# fact-atmega32u4.net
KiCad netlist of a schematic drawn in EAGLE
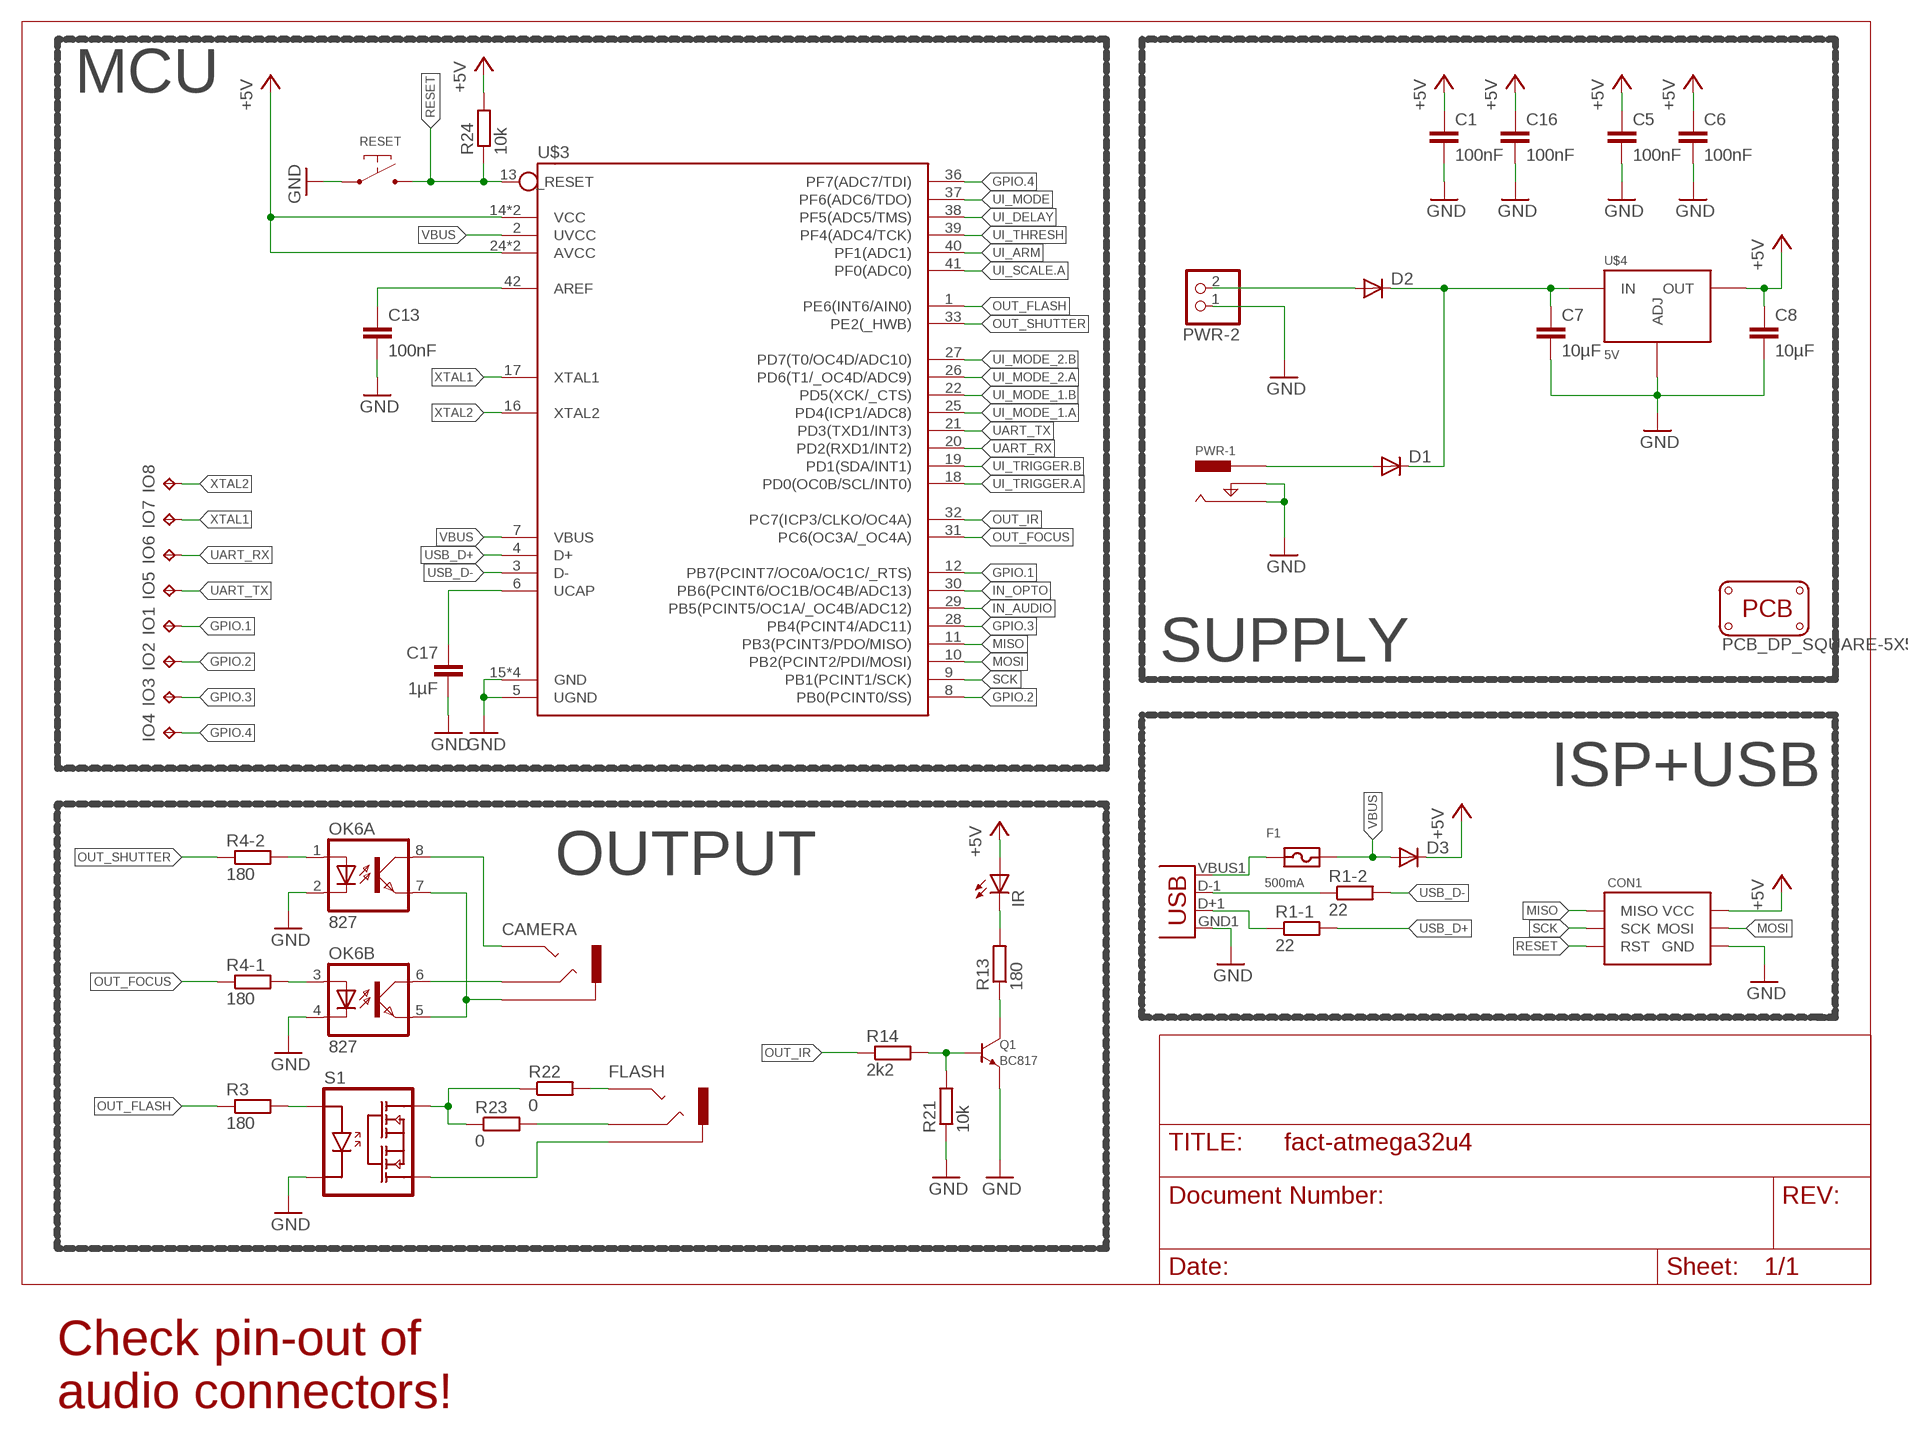
[diagram p0: schematic, sheet 1, part 1 of 2]
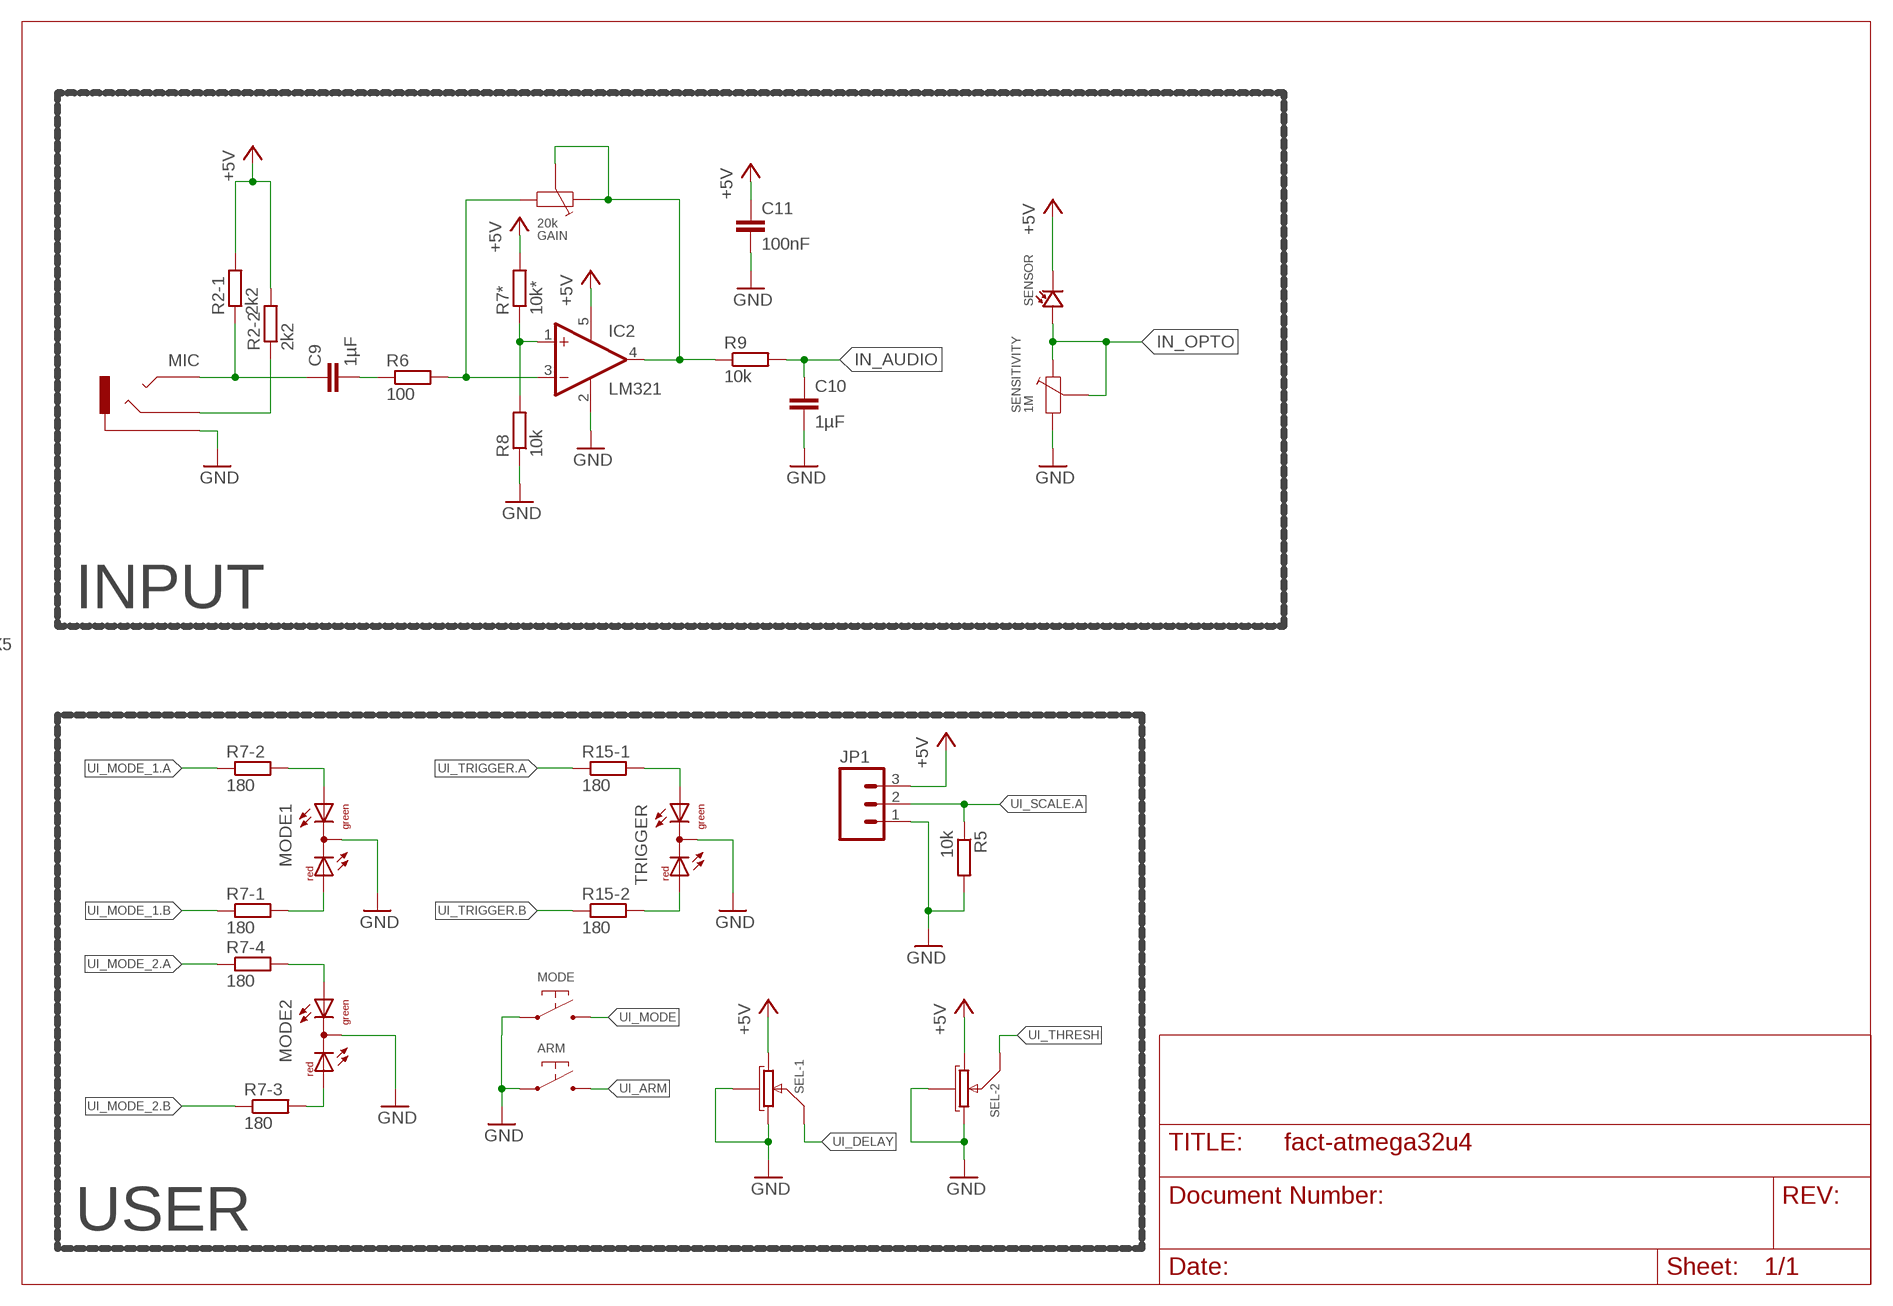
[diagram p1: schematic, sheet 1, part 2 of 2]

(export (version "E")
  (design (tool "Eeschema 10.0.6"))
  (components
    (comp (ref "ARM")
      (value "SWITCH-DEFAULT_OFF-DEFAULT")
      (footprint "eagle-import:SWITCH-GENERIC-4_PIN")
      (libsource (lib "eagle-import") (part "SWITCH-DEFAULT_OFF-DEFAULT"))
    )
    (comp (ref "C1")
      (value "100nF")
      (footprint "eagle-import:C0603")
      (libsource (lib "eagle-import") (part "C-EUC0603"))
    )
    (comp (ref "C5")
      (value "100nF")
      (footprint "eagle-import:C0603")
      (libsource (lib "eagle-import") (part "C-EUC0603"))
    )
    (comp (ref "C6")
      (value "100nF")
      (footprint "eagle-import:C0603")
      (libsource (lib "eagle-import") (part "C-EUC0603"))
    )
    (comp (ref "C7")
      (value "10µF")
      (footprint "eagle-import:C0603")
      (libsource (lib "eagle-import") (part "C-EUC0603"))
    )
    (comp (ref "C8")
      (value "10µF")
      (footprint "eagle-import:C0603")
      (libsource (lib "eagle-import") (part "C-EUC0603"))
    )
    (comp (ref "C9")
      (value "1µF")
      (footprint "eagle-import:C0603")
      (libsource (lib "eagle-import") (part "C-EUC0603"))
    )
    (comp (ref "C10")
      (value "1µF")
      (footprint "eagle-import:C0603")
      (libsource (lib "eagle-import") (part "C-EUC0603"))
    )
    (comp (ref "C11")
      (value "100nF")
      (footprint "eagle-import:C0603")
      (libsource (lib "eagle-import") (part "C-EUC0603"))
    )
    (comp (ref "C13")
      (value "100nF")
      (footprint "eagle-import:C0603")
      (libsource (lib "eagle-import") (part "C-EUC0603"))
    )
    (comp (ref "C16")
      (value "100nF")
      (footprint "eagle-import:C0603")
      (libsource (lib "eagle-import") (part "C-EUC0603"))
    )
    (comp (ref "C17")
      (value "1µF")
      (footprint "eagle-import:C0603")
      (libsource (lib "eagle-import") (part "C-EUC0603"))
    )
    (comp (ref "CAMERA")
      (value "AUDIO-STEREO2MM5")
      (footprint "eagle-import:AUDIO-STEREO-2MM5-SJ1-2503A")
      (libsource (lib "eagle-import") (part "AUDIO-STEREO2MM5"))
    )
    (comp (ref "CON1")
      (value "ISP-6_PIN-POGO")
      (footprint "eagle-import:POGO-1.27-6_PIN-MADWORM")
      (libsource (lib "eagle-import") (part "ISP-6_PIN-POGO"))
    )
    (comp (ref "D1")
      (value "DIODESOD")
      (footprint "eagle-import:SOD-323")
      (libsource (lib "eagle-import") (part "DIODESOD"))
    )
    (comp (ref "D2")
      (value "DIODESOD")
      (footprint "eagle-import:SOD-323")
      (libsource (lib "eagle-import") (part "DIODESOD"))
    )
    (comp (ref "D3")
      (value "DIODESOD")
      (footprint "eagle-import:SOD-323")
      (libsource (lib "eagle-import") (part "DIODESOD"))
    )
    (comp (ref "F1")
      (value "500mA")
      (footprint "eagle-import:SMD-0805")
      (libsource (lib "eagle-import") (part "FUSE0805"))
    )
    (comp (ref "FLASH")
      (value "AUDIO-STEREODEALEXTREME")
      (footprint "eagle-import:AUDIO-STEREO-3MM5-ST-009")
      (libsource (lib "eagle-import") (part "AUDIO-STEREODEALEXTREME"))
    )
    (comp (ref "GAIN")
      (value "20k")
      (footprint "eagle-import:TRIM-POT-CA6-VS5")
      (libsource (lib "eagle-import") (part "TRIM-POT"))
    )
    (comp (ref "IC2")
      (value "LM321")
      (footprint "eagle-import:SOT23-5")
      (libsource (lib "eagle-import") (part "LM321?MF"))
    )
    (comp (ref "IO1")
      (value "TPTP15R")
      (footprint "eagle-import:TP15R")
      (libsource (lib "eagle-import") (part "TPTP15R"))
    )
    (comp (ref "IO2")
      (value "TPTP15R")
      (footprint "eagle-import:TP15R")
      (libsource (lib "eagle-import") (part "TPTP15R"))
    )
    (comp (ref "IO3")
      (value "TPTP15R")
      (footprint "eagle-import:TP15R")
      (libsource (lib "eagle-import") (part "TPTP15R"))
    )
    (comp (ref "IO4")
      (value "TPTP15R")
      (footprint "eagle-import:TP15R")
      (libsource (lib "eagle-import") (part "TPTP15R"))
    )
    (comp (ref "IO5")
      (value "TPTP15R")
      (footprint "eagle-import:TP15R")
      (libsource (lib "eagle-import") (part "TPTP15R"))
    )
    (comp (ref "IO6")
      (value "TPTP15R")
      (footprint "eagle-import:TP15R")
      (libsource (lib "eagle-import") (part "TPTP15R"))
    )
    (comp (ref "IO7")
      (value "TPTP15R")
      (footprint "eagle-import:TP15R")
      (libsource (lib "eagle-import") (part "TPTP15R"))
    )
    (comp (ref "IO8")
      (value "TPTP15R")
      (footprint "eagle-import:TP15R")
      (libsource (lib "eagle-import") (part "TPTP15R"))
    )
    (comp (ref "IR")
      (value "LED5MM")
      (footprint "eagle-import:LED5MM")
      (libsource (lib "eagle-import") (part "LED5MM"))
    )
    (comp (ref "JP1")
      (value "M03LOCK")
      (footprint "eagle-import:1X03_LOCK")
      (libsource (lib "eagle-import") (part "M03LOCK"))
    )
    (comp (ref "MIC")
      (value "AUDIO-STEREODEALEXTREME")
      (footprint "eagle-import:AUDIO-STEREO-3MM5-ST-009")
      (libsource (lib "eagle-import") (part "AUDIO-STEREODEALEXTREME"))
    )
    (comp (ref "MODE")
      (value "SWITCH-DEFAULT_OFF-DEFAULT")
      (footprint "eagle-import:SWITCH-GENERIC-4_PIN")
      (libsource (lib "eagle-import") (part "SWITCH-DEFAULT_OFF-DEFAULT"))
    )
    (comp (ref "MODE1")
      (value "DUOLED-RG-C")
      (footprint "eagle-import:DUOLED-C-5MM")
      (libsource (lib "eagle-import") (part "DUOLED-RG-C"))
    )
    (comp (ref "MODE2")
      (value "DUOLED-RG-C")
      (footprint "eagle-import:DUOLED-C-5MM")
      (libsource (lib "eagle-import") (part "DUOLED-RG-C"))
    )
    (comp (ref "OK6")
      (value "827")
      (footprint "eagle-import:SMD08")
      (libsource (lib "eagle-import") (part "OPTOCOUPLER-PC827SMD"))
    )
    (comp (ref "PCB1")
      (value "PCB_DP_SQUARE-5X5")
      (footprint "eagle-import:DP5050_V1")
      (libsource (lib "eagle-import") (part "PCB_DP_SQUARE-5X5"))
    )
    (comp (ref "PWR-1")
      (value "POWER-BARREL_JACKEBAY")
      (footprint "eagle-import:POWER-BARREL-2MM1-EBAY")
      (libsource (lib "eagle-import") (part "POWER-BARREL_JACKEBAY"))
    )
    (comp (ref "PWR-2")
      (value "PINHD-1X2")
      (footprint "eagle-import:1X02")
      (libsource (lib "eagle-import") (part "PINHD-1X2"))
    )
    (comp (ref "Q1")
      (value "BC817")
      (footprint "eagle-import:SOT23")
      (libsource (lib "eagle-import") (part "TRANSISTOR-NPN-GENERIC-BEC"))
    )
    (comp (ref "R1")
      (value "22")
      (footprint "eagle-import:R-ARRAY-2X-0603")
      (libsource (lib "eagle-import") (part "R-ARRAY-2X-0603"))
    )
    (comp (ref "R2")
      (value "2k2")
      (footprint "eagle-import:R-ARRAY-2X-0603")
      (libsource (lib "eagle-import") (part "R-ARRAY-2X-0603"))
    )
    (comp (ref "R3")
      (value "180")
      (footprint "eagle-import:R0603")
      (libsource (lib "eagle-import") (part "R-EU_R0603"))
    )
    (comp (ref "R4")
      (value "180")
      (footprint "eagle-import:R-ARRAY-2X-0603")
      (libsource (lib "eagle-import") (part "R-ARRAY-2X-0603"))
    )
    (comp (ref "R5")
      (value "10k")
      (footprint "eagle-import:R0603")
      (libsource (lib "eagle-import") (part "R-EU_R0603"))
    )
    (comp (ref "R6")
      (value "100")
      (footprint "eagle-import:R0603")
      (libsource (lib "eagle-import") (part "R-EU_R0603"))
    )
    (comp (ref "R7")
      (value "180")
      (footprint "eagle-import:R-ARRAY-4X-CTS-0603")
      (libsource (lib "eagle-import") (part "R-ARRAY-4X0603"))
    )
    (comp (ref "R7*")
      (value "10k*")
      (footprint "eagle-import:R0603")
      (libsource (lib "eagle-import") (part "R-EU_R0603"))
    )
    (comp (ref "R8")
      (value "10k")
      (footprint "eagle-import:R0603")
      (libsource (lib "eagle-import") (part "R-EU_R0603"))
    )
    (comp (ref "R9")
      (value "10k")
      (footprint "eagle-import:R0603")
      (libsource (lib "eagle-import") (part "R-EU_R0603"))
    )
    (comp (ref "R13")
      (value "180")
      (footprint "eagle-import:R0603")
      (libsource (lib "eagle-import") (part "R-EU_R0603"))
    )
    (comp (ref "R14")
      (value "2k2")
      (footprint "eagle-import:R0603")
      (libsource (lib "eagle-import") (part "R-EU_R0603"))
    )
    (comp (ref "R15")
      (value "180")
      (footprint "eagle-import:R-ARRAY-2X-0603")
      (libsource (lib "eagle-import") (part "R-ARRAY-2X-0603"))
    )
    (comp (ref "R21")
      (value "10k")
      (footprint "eagle-import:R0603")
      (libsource (lib "eagle-import") (part "R-EU_R0603"))
    )
    (comp (ref "R22")
      (value "0")
      (footprint "eagle-import:R1206")
      (libsource (lib "eagle-import") (part "rcl_R-EU_R1206"))
    )
    (comp (ref "R23")
      (value "0")
      (footprint "eagle-import:R1206")
      (libsource (lib "eagle-import") (part "rcl_R-EU_R1206"))
    )
    (comp (ref "R24")
      (value "10k")
      (footprint "eagle-import:R0603")
      (libsource (lib "eagle-import") (part "R-EU_R0603"))
    )
    (comp (ref "RESET")
      (value "SWITCH-DEFAULT_OFF-SMD-2_PIN")
      (footprint "eagle-import:SWITCH-SMD-2_PIN-DX")
      (libsource (lib "eagle-import") (part "SWITCH-DEFAULT_OFF-SMD-2_PIN"))
    )
    (comp (ref "S1")
      (value "RELAYLH1500")
      (footprint "eagle-import:SMD-06")
      (libsource (lib "eagle-import") (part "RELAYLH1500"))
    )
    (comp (ref "SEL")
      (value "DUAL-POT")
      (footprint "eagle-import:POT-DUAL-P090")
      (libsource (lib "eagle-import") (part "DUAL-POT"))
    )
    (comp (ref "SENSITIVITY")
      (value "1M")
      (footprint "eagle-import:TRIM-POT-CA6-VS5")
      (libsource (lib "eagle-import") (part "TRIM-POT"))
    )
    (comp (ref "SENSOR")
      (value "PHOTODIODE")
      (footprint "eagle-import:LED-5MM")
      (libsource (lib "eagle-import") (part "PHOTODIODE"))
    )
    (comp (ref "TRIGGER")
      (value "DUOLED-RG-C")
      (footprint "eagle-import:DUOLED-C-5MM")
      (libsource (lib "eagle-import") (part "DUOLED-RG-C"))
    )
    (comp (ref "U$3")
      (value "ATMEGA32U4-QFN-HAND")
      (footprint "eagle-import:QFN-44-NOPAD-LONGLEADS")
      (libsource (lib "eagle-import") (part "ATMEGA32U4-QFN-HAND"))
    )
    (comp (ref "U$4")
      (value "5V")
      (footprint "eagle-import:SOT223")
      (libsource (lib "eagle-import") (part "REGULATOR-TLV1117SOT223"))
    )
    (comp (ref "U$5")
      (value "USB")
      (footprint "eagle-import:USB-AB-MICRO-SMD_V03")
      (libsource (lib "eagle-import") (part "USB"))
    )
  )
  (nets
    (net (code "1") (name "+5V") (class "Default")
      (node (ref "C1") (pin "1") (pinfunction "1_1") (pintype "passive"))
      (node (ref "C11") (pin "1") (pinfunction "1_1") (pintype "passive"))
      (node (ref "C16") (pin "1") (pinfunction "1_1") (pintype "passive"))
      (node (ref "C5") (pin "1") (pinfunction "1_1") (pintype "passive"))
      (node (ref "C6") (pin "1") (pinfunction "1_1") (pintype "passive"))
      (node (ref "C8") (pin "1") (pinfunction "1_1") (pintype "passive"))
      (node (ref "CON1") (pin "P$2") (pinfunction "VCC_P$2") (pintype "power_in"))
      (node (ref "D3") (pin "1") (pinfunction "C_1") (pintype "passive"))
      (node (ref "IC2") (pin "5") (pinfunction "V+_5") (pintype "power_in"))
      (node (ref "IR") (pin "A") (pinfunction "A_A") (pintype "passive"))
      (node (ref "JP1") (pin "3") (pinfunction "3_3") (pintype "passive"))
      (node (ref "R2") (pin "P$1.2") (pinfunction "2_P$1.2") (pintype "passive"))
      (node (ref "R2") (pin "P$2.2") (pinfunction "2_P$2.2") (pintype "passive"))
      (node (ref "R24") (pin "2") (pinfunction "2_2") (pintype "passive"))
      (node (ref "R7*") (pin "2") (pinfunction "2_2") (pintype "passive"))
      (node (ref "SEL") (pin "P1-3") (pinfunction "B_P1-3") (pintype "bidirectional"))
      (node (ref "SEL") (pin "P2-1") (pinfunction "A_P2-1") (pintype "bidirectional"))
      (node (ref "SENSOR") (pin "K") (pinfunction "C_K") (pintype "bidirectional"))
      (node (ref "U$3") (pin "14") (pinfunction "VCC_14") (pintype "bidirectional"))
      (node (ref "U$3") (pin "24") (pinfunction "AVCC_24") (pintype "bidirectional"))
      (node (ref "U$3") (pin "34") (pinfunction "VCC_34") (pintype "bidirectional"))
      (node (ref "U$3") (pin "44") (pinfunction "AVCC_44") (pintype "bidirectional"))
      (node (ref "U$4") (pin "2") (pinfunction "OUT_2") (pintype "bidirectional"))
      (node (ref "U$4") (pin "4") (pinfunction "OUT_4") (pintype "bidirectional"))
    )
    (net (code "2") (name "GND") (class "Default")
      (node (ref "ARM") (pin "P$1") (pinfunction "P$1_P$1") (pintype "bidirectional"))
      (node (ref "ARM") (pin "P$2") (pinfunction "P$1_P$2") (pintype "bidirectional"))
      (node (ref "C1") (pin "2") (pinfunction "2_2") (pintype "passive"))
      (node (ref "C10") (pin "2") (pinfunction "2_2") (pintype "passive"))
      (node (ref "C11") (pin "2") (pinfunction "2_2") (pintype "passive"))
      (node (ref "C13") (pin "2") (pinfunction "2_2") (pintype "passive"))
      (node (ref "C16") (pin "2") (pinfunction "2_2") (pintype "passive"))
      (node (ref "C17") (pin "2") (pinfunction "2_2") (pintype "passive"))
      (node (ref "C5") (pin "2") (pinfunction "2_2") (pintype "passive"))
      (node (ref "C6") (pin "2") (pinfunction "2_2") (pintype "passive"))
      (node (ref "C7") (pin "2") (pinfunction "2_2") (pintype "passive"))
      (node (ref "C8") (pin "2") (pinfunction "2_2") (pintype "passive"))
      (node (ref "CON1") (pin "P$6") (pinfunction "GND_P$6") (pintype "power_in"))
      (node (ref "IC2") (pin "2") (pinfunction "V-_2") (pintype "power_in"))
      (node (ref "JP1") (pin "1") (pinfunction "1_1") (pintype "passive"))
      (node (ref "MIC") (pin "P$1.1") (pinfunction "SLEEVE_P$1.1") (pintype "passive"))
      (node (ref "MIC") (pin "P$1.2") (pinfunction "SLEEVE_P$1.2") (pintype "passive"))
      (node (ref "MODE") (pin "P$1") (pinfunction "P$1_P$1") (pintype "bidirectional"))
      (node (ref "MODE") (pin "P$2") (pinfunction "P$1_P$2") (pintype "bidirectional"))
      (node (ref "MODE1") (pin "C") (pinfunction "C_C") (pintype "passive"))
      (node (ref "MODE2") (pin "C") (pinfunction "C_C") (pintype "passive"))
      (node (ref "OK6") (pin "2") (pinfunction "C_2") (pintype "passive"))
      (node (ref "OK6") (pin "4") (pinfunction "C_4") (pintype "passive"))
      (node (ref "PWR-1") (pin "P$2") (pinfunction "SWITCH_P$2") (pintype "bidirectional"))
      (node (ref "PWR-1") (pin "P$3") (pinfunction "OUTER_P$3") (pintype "bidirectional"))
      (node (ref "PWR-2") (pin "1") (pinfunction "1_1") (pintype "passive"))
      (node (ref "Q1") (pin "P$2") (pinfunction "EMITTER_P$2") (pintype "bidirectional"))
      (node (ref "R21") (pin "1") (pinfunction "1_1") (pintype "passive"))
      (node (ref "R5") (pin "2") (pinfunction "2_2") (pintype "passive"))
      (node (ref "R8") (pin "1") (pinfunction "1_1") (pintype "passive"))
      (node (ref "RESET") (pin "P$1") (pinfunction "P$1_P$1") (pintype "bidirectional"))
      (node (ref "S1") (pin "2") (pinfunction "LED-C_2") (pintype "bidirectional"))
      (node (ref "SEL") (pin "CENTER") (pinfunction "SHIELD_CENTER") (pintype "bidirectional"))
      (node (ref "SEL") (pin "G1-S") (pinfunction "SHIELD_G1-S") (pintype "bidirectional"))
      (node (ref "SEL") (pin "G2-S") (pinfunction "SHIELD_G2-S") (pintype "bidirectional"))
      (node (ref "SEL") (pin "P1-1") (pinfunction "A_P1-1") (pintype "bidirectional"))
      (node (ref "SEL") (pin "P2-3") (pinfunction "B_P2-3") (pintype "bidirectional"))
      (node (ref "SENSITIVITY") (pin "P$2") (pinfunction "P$2_P$2") (pintype "bidirectional"))
      (node (ref "TRIGGER") (pin "C") (pinfunction "C_C") (pintype "passive"))
      (node (ref "U$3") (pin "15") (pinfunction "GND_15") (pintype "bidirectional"))
      (node (ref "U$3") (pin "23") (pinfunction "GND_23") (pintype "bidirectional"))
      (node (ref "U$3") (pin "35") (pinfunction "GND_35") (pintype "bidirectional"))
      (node (ref "U$3") (pin "43") (pinfunction "GND_43") (pintype "bidirectional"))
      (node (ref "U$3") (pin "5") (pinfunction "UGND_5") (pintype "bidirectional"))
      (node (ref "U$4") (pin "1") (pinfunction "ADJ_1") (pintype "bidirectional"))
      (node (ref "U$5") (pin "GND1") (pinfunction "GND_GND1") (pintype "bidirectional"))
    )
    (net (code "3") (name "GPIO.1") (class "Default")
      (node (ref "IO1") (pin "TP") (pinfunction "TP_TP") (pintype "input"))
      (node (ref "U$3") (pin "12") (pinfunction "PB7(PCINT7/OC0A/OC1C/_RTS)_12") (pintype "bidirectional"))
    )
    (net (code "4") (name "GPIO.2") (class "Default")
      (node (ref "IO2") (pin "TP") (pinfunction "TP_TP") (pintype "input"))
      (node (ref "U$3") (pin "8") (pinfunction "PB0(PCINT0/SS)_8") (pintype "bidirectional"))
    )
    (net (code "5") (name "GPIO.3") (class "Default")
      (node (ref "IO3") (pin "TP") (pinfunction "TP_TP") (pintype "input"))
      (node (ref "U$3") (pin "28") (pinfunction "PB4(PCINT4/ADC11)_28") (pintype "bidirectional"))
    )
    (net (code "6") (name "GPIO.4") (class "Default")
      (node (ref "IO4") (pin "TP") (pinfunction "TP_TP") (pintype "input"))
      (node (ref "U$3") (pin "36") (pinfunction "PF7(ADC7/TDI)_36") (pintype "bidirectional"))
    )
    (net (code "7") (name "IN_AUDIO") (class "Default")
      (node (ref "C10") (pin "1") (pinfunction "1_1") (pintype "passive"))
      (node (ref "R9") (pin "2") (pinfunction "2_2") (pintype "passive"))
      (node (ref "U$3") (pin "29") (pinfunction "PB5(PCINT5/OC1A/_OC4B/ADC12)_29") (pintype "bidirectional"))
    )
    (net (code "8") (name "IN_OPTO") (class "Default")
      (node (ref "SENSITIVITY") (pin "CENTER") (pinfunction "CENTER_CENTER") (pintype "bidirectional"))
      (node (ref "SENSITIVITY") (pin "P$1") (pinfunction "P$1_P$1") (pintype "bidirectional"))
      (node (ref "SENSOR") (pin "A") (pinfunction "A_A") (pintype "bidirectional"))
      (node (ref "U$3") (pin "30") (pinfunction "PB6(PCINT6/OC1B/OC4B/ADC13)_30") (pintype "bidirectional"))
    )
    (net (code "9") (name "MISO") (class "Default")
      (node (ref "CON1") (pin "P$1") (pinfunction "MISO_P$1") (pintype "bidirectional"))
      (node (ref "U$3") (pin "11") (pinfunction "PB3(PCINT3/PDO/MISO)_11") (pintype "bidirectional"))
    )
    (net (code "10") (name "MOSI") (class "Default")
      (node (ref "CON1") (pin "P$4") (pinfunction "MOSI_P$4") (pintype "bidirectional"))
      (node (ref "U$3") (pin "10") (pinfunction "PB2(PCINT2/PDI/MOSI)_10") (pintype "bidirectional"))
    )
    (net (code "11") (name "Net-(C9-Pad2)") (class "Default")
      (node (ref "C9") (pin "2") (pinfunction "2_2") (pintype "passive"))
      (node (ref "R6") (pin "1") (pinfunction "1_1") (pintype "passive"))
    )
    (net (code "12") (name "Net-(CAMERA-RING)") (class "Default")
      (node (ref "CAMERA") (pin "P$4") (pinfunction "RING_P$4") (pintype "passive"))
      (node (ref "OK6") (pin "6") (pinfunction "COL_6") (pintype "passive"))
    )
    (net (code "13") (name "Net-(CAMERA-SLEEVE)") (class "Default")
      (node (ref "CAMERA") (pin "P$1") (pinfunction "SLEEVE_P$1") (pintype "passive"))
      (node (ref "OK6") (pin "5") (pinfunction "EMIT_5") (pintype "passive"))
      (node (ref "OK6") (pin "7") (pinfunction "EMIT_7") (pintype "passive"))
    )
    (net (code "14") (name "Net-(D1-A)") (class "Default")
      (node (ref "D1") (pin "2") (pinfunction "A_2") (pintype "passive"))
      (node (ref "PWR-1") (pin "P$4") (pinfunction "CENTER_P$4") (pintype "bidirectional"))
    )
    (net (code "15") (name "Net-(D1-C)") (class "Default")
      (node (ref "C7") (pin "1") (pinfunction "1_1") (pintype "passive"))
      (node (ref "D1") (pin "1") (pinfunction "C_1") (pintype "passive"))
      (node (ref "D2") (pin "1") (pinfunction "C_1") (pintype "passive"))
      (node (ref "U$4") (pin "3") (pinfunction "IN_3") (pintype "bidirectional"))
    )
    (net (code "16") (name "Net-(D2-A)") (class "Default")
      (node (ref "D2") (pin "2") (pinfunction "A_2") (pintype "passive"))
      (node (ref "PWR-2") (pin "2") (pinfunction "2_2") (pintype "passive"))
    )
    (net (code "17") (name "Net-(F1-P$1)") (class "Default")
      (node (ref "F1") (pin "1") (pinfunction "P$1_1") (pintype "bidirectional"))
      (node (ref "U$5") (pin "VBUS1") (pinfunction "VBUS_VBUS1") (pintype "bidirectional"))
    )
    (net (code "18") (name "Net-(FLASH-RING)") (class "Default")
      (node (ref "FLASH") (pin "P$2") (pinfunction "RING_P$2") (pintype "passive"))
      (node (ref "R23") (pin "2") (pinfunction "2_2") (pintype "passive"))
    )
    (net (code "19") (name "Net-(FLASH-TIP-PadP$3.1)") (class "Default")
      (node (ref "FLASH") (pin "P$3.1") (pinfunction "TIP_P$3.1") (pintype "passive"))
      (node (ref "FLASH") (pin "P$3.2") (pinfunction "TIP_P$3.2") (pintype "passive"))
      (node (ref "R22") (pin "2") (pinfunction "2_2") (pintype "passive"))
    )
    (net (code "20") (name "Net-(IC2-+IN)") (class "Default")
      (node (ref "IC2") (pin "1") (pinfunction "+IN_1") (pintype "input"))
      (node (ref "R7*") (pin "1") (pinfunction "1_1") (pintype "passive"))
      (node (ref "R8") (pin "2") (pinfunction "2_2") (pintype "passive"))
    )
    (net (code "21") (name "Net-(IC2--IN)") (class "Default")
      (node (ref "GAIN") (pin "P$2") (pinfunction "P$2_P$2") (pintype "bidirectional"))
      (node (ref "IC2") (pin "3") (pinfunction "-IN_3") (pintype "input"))
      (node (ref "R6") (pin "2") (pinfunction "2_2") (pintype "passive"))
    )
    (net (code "22") (name "Net-(IC2-OUT)") (class "Default")
      (node (ref "GAIN") (pin "CENTER") (pinfunction "CENTER_CENTER") (pintype "bidirectional"))
      (node (ref "GAIN") (pin "P$1") (pinfunction "P$1_P$1") (pintype "bidirectional"))
      (node (ref "IC2") (pin "4") (pinfunction "OUT_4") (pintype "output"))
      (node (ref "R9") (pin "1") (pinfunction "1_1") (pintype "passive"))
    )
    (net (code "23") (name "Net-(IR-C)") (class "Default")
      (node (ref "IR") (pin "K") (pinfunction "C_K") (pintype "passive"))
      (node (ref "R13") (pin "2") (pinfunction "2_2") (pintype "passive"))
    )
    (net (code "24") (name "Net-(MIC-RING)") (class "Default")
      (node (ref "MIC") (pin "P$2") (pinfunction "RING_P$2") (pintype "passive"))
      (node (ref "R2") (pin "P$2.1") (pinfunction "1_P$2.1") (pintype "passive"))
    )
    (net (code "25") (name "Net-(MODE1-AG)") (class "Default")
      (node (ref "MODE1") (pin "AX") (pinfunction "AG_AX") (pintype "passive"))
      (node (ref "R7") (pin "P$2.2") (pinfunction "2_P$2.2") (pintype "passive"))
    )
    (net (code "26") (name "Net-(MODE2-AG)") (class "Default")
      (node (ref "MODE2") (pin "AX") (pinfunction "AG_AX") (pintype "passive"))
      (node (ref "R7") (pin "P$4.2") (pinfunction "2_P$4.2") (pintype "passive"))
    )
    (net (code "27") (name "Net-(OK6A-A)") (class "Default")
      (node (ref "OK6") (pin "1") (pinfunction "A_1") (pintype "passive"))
      (node (ref "R4") (pin "P$2.2") (pinfunction "2_P$2.2") (pintype "passive"))
    )
    (net (code "28") (name "Net-(OK6A-COL)") (class "Default")
      (node (ref "CAMERA") (pin "P$2") (pinfunction "TIP_P$2") (pintype "passive"))
      (node (ref "CAMERA") (pin "P$3") (pinfunction "TIP_P$3") (pintype "passive"))
      (node (ref "OK6") (pin "8") (pinfunction "COL_8") (pintype "passive"))
    )
    (net (code "29") (name "Net-(OK6B-A)") (class "Default")
      (node (ref "OK6") (pin "3") (pinfunction "A_3") (pintype "passive"))
      (node (ref "R4") (pin "P$1.2") (pinfunction "2_P$1.2") (pintype "passive"))
    )
    (net (code "30") (name "Net-(Q1-BASE)") (class "Default")
      (node (ref "Q1") (pin "P$1") (pinfunction "BASE_P$1") (pintype "bidirectional"))
      (node (ref "R14") (pin "2") (pinfunction "2_2") (pintype "passive"))
      (node (ref "R21") (pin "2") (pinfunction "2_2") (pintype "passive"))
    )
    (net (code "31") (name "Net-(Q1-COLLECTOR)") (class "Default")
      (node (ref "Q1") (pin "P$3") (pinfunction "COLLECTOR_P$3") (pintype "bidirectional"))
      (node (ref "R13") (pin "1") (pinfunction "1_1") (pintype "passive"))
    )
    (net (code "32") (name "Net-(R1A-1)") (class "Default")
      (node (ref "R1") (pin "P$1.1") (pinfunction "1_P$1.1") (pintype "passive"))
      (node (ref "U$5") (pin "D+1") (pinfunction "D+_D+1") (pintype "bidirectional"))
    )
    (net (code "33") (name "Net-(R1B-1)") (class "Default")
      (node (ref "R1") (pin "P$2.1") (pinfunction "1_P$2.1") (pintype "passive"))
      (node (ref "U$5") (pin "D-1") (pinfunction "D-_D-1") (pintype "bidirectional"))
    )
    (net (code "34") (name "Net-(R2A-1)") (class "Default")
      (node (ref "C9") (pin "1") (pinfunction "1_1") (pintype "passive"))
      (node (ref "MIC") (pin "P$3.1") (pinfunction "TIP_P$3.1") (pintype "passive"))
      (node (ref "MIC") (pin "P$3.2") (pinfunction "TIP_P$3.2") (pintype "passive"))
      (node (ref "R2") (pin "P$1.1") (pinfunction "1_P$1.1") (pintype "passive"))
    )
    (net (code "35") (name "Net-(R7A-2)") (class "Default")
      (node (ref "MODE1") (pin "AR") (pinfunction "AR_AR") (pintype "passive"))
      (node (ref "R7") (pin "P$1.2") (pinfunction "2_P$1.2") (pintype "passive"))
    )
    (net (code "36") (name "Net-(R7C-2)") (class "Default")
      (node (ref "MODE2") (pin "AR") (pinfunction "AR_AR") (pintype "passive"))
      (node (ref "R7") (pin "P$3.2") (pinfunction "2_P$3.2") (pintype "passive"))
    )
    (net (code "37") (name "Net-(R15A-2)") (class "Default")
      (node (ref "R15") (pin "P$1.2") (pinfunction "2_P$1.2") (pintype "passive"))
      (node (ref "TRIGGER") (pin "AX") (pinfunction "AG_AX") (pintype "passive"))
    )
    (net (code "38") (name "Net-(R15B-2)") (class "Default")
      (node (ref "R15") (pin "P$2.2") (pinfunction "2_P$2.2") (pintype "passive"))
      (node (ref "TRIGGER") (pin "AR") (pinfunction "AR_AR") (pintype "passive"))
    )
    (net (code "39") (name "Net-(S1-LED-A)") (class "Default")
      (node (ref "R3") (pin "2") (pinfunction "2_2") (pintype "passive"))
      (node (ref "S1") (pin "1") (pinfunction "LED-A_1") (pintype "bidirectional"))
    )
    (net (code "40") (name "Net-(S1-R1)") (class "Default")
      (node (ref "R22") (pin "1") (pinfunction "1_1") (pintype "passive"))
      (node (ref "R23") (pin "1") (pinfunction "1_1") (pintype "passive"))
      (node (ref "S1") (pin "6") (pinfunction "R1_6") (pintype "bidirectional"))
    )
    (net (code "41") (name "Net-(S1-R2)") (class "Default")
      (node (ref "FLASH") (pin "P$1.1") (pinfunction "SLEEVE_P$1.1") (pintype "passive"))
      (node (ref "FLASH") (pin "P$1.2") (pinfunction "SLEEVE_P$1.2") (pintype "passive"))
      (node (ref "S1") (pin "4") (pinfunction "R2_4") (pintype "bidirectional"))
    )
    (net (code "42") (name "Net-(U$3-AREF)") (class "Default")
      (node (ref "C13") (pin "1") (pinfunction "1_1") (pintype "passive"))
      (node (ref "U$3") (pin "42") (pinfunction "AREF_42") (pintype "bidirectional"))
    )
    (net (code "43") (name "Net-(U$3-UCAP)") (class "Default")
      (node (ref "C17") (pin "1") (pinfunction "1_1") (pintype "passive"))
      (node (ref "U$3") (pin "6") (pinfunction "UCAP_6") (pintype "bidirectional"))
    )
    (net (code "44") (name "OUT_FLASH") (class "Default")
      (node (ref "R3") (pin "1") (pinfunction "1_1") (pintype "passive"))
      (node (ref "U$3") (pin "1") (pinfunction "PE6(INT6/AIN0)_1") (pintype "bidirectional"))
    )
    (net (code "45") (name "OUT_FOCUS") (class "Default")
      (node (ref "R4") (pin "P$1.1") (pinfunction "1_P$1.1") (pintype "passive"))
      (node (ref "U$3") (pin "31") (pinfunction "PC6(OC3A/_OC4A)_31") (pintype "bidirectional"))
    )
    (net (code "46") (name "OUT_IR") (class "Default")
      (node (ref "R14") (pin "1") (pinfunction "1_1") (pintype "passive"))
      (node (ref "U$3") (pin "32") (pinfunction "PC7(ICP3/CLKO/OC4A)_32") (pintype "bidirectional"))
    )
    (net (code "47") (name "OUT_SHUTTER") (class "Default")
      (node (ref "R4") (pin "P$2.1") (pinfunction "1_P$2.1") (pintype "passive"))
      (node (ref "U$3") (pin "33") (pinfunction "PE2(_HWB)_33") (pintype "bidirectional"))
    )
    (net (code "48") (name "RESET") (class "Default")
      (node (ref "CON1") (pin "P$5") (pinfunction "RST_P$5") (pintype "bidirectional"))
      (node (ref "R24") (pin "1") (pinfunction "1_1") (pintype "passive"))
      (node (ref "RESET") (pin "P$2") (pinfunction "P$2_P$2") (pintype "bidirectional"))
      (node (ref "U$3") (pin "13") (pinfunction "_RESET_13") (pintype "bidirectional"))
    )
    (net (code "49") (name "SCK") (class "Default")
      (node (ref "CON1") (pin "P$3") (pinfunction "SCK_P$3") (pintype "bidirectional"))
      (node (ref "U$3") (pin "9") (pinfunction "PB1(PCINT1/SCK)_9") (pintype "bidirectional"))
    )
    (net (code "50") (name "UART_RX") (class "Default")
      (node (ref "IO6") (pin "TP") (pinfunction "TP_TP") (pintype "input"))
      (node (ref "U$3") (pin "20") (pinfunction "PD2(RXD1/INT2)_20") (pintype "bidirectional"))
    )
    (net (code "51") (name "UART_TX") (class "Default")
      (node (ref "IO5") (pin "TP") (pinfunction "TP_TP") (pintype "input"))
      (node (ref "U$3") (pin "21") (pinfunction "PD3(TXD1/INT3)_21") (pintype "bidirectional"))
    )
    (net (code "52") (name "UI_ARM") (class "Default")
      (node (ref "ARM") (pin "P$3") (pinfunction "P$2_P$3") (pintype "bidirectional"))
      (node (ref "ARM") (pin "P$4") (pinfunction "P$2_P$4") (pintype "bidirectional"))
      (node (ref "U$3") (pin "40") (pinfunction "PF1(ADC1)_40") (pintype "bidirectional"))
    )
    (net (code "53") (name "UI_DELAY") (class "Default")
      (node (ref "SEL") (pin "P1-2") (pinfunction "M_P1-2") (pintype "bidirectional"))
      (node (ref "U$3") (pin "38") (pinfunction "PF5(ADC5/TMS)_38") (pintype "bidirectional"))
    )
    (net (code "54") (name "UI_MODE") (class "Default")
      (node (ref "MODE") (pin "P$3") (pinfunction "P$2_P$3") (pintype "bidirectional"))
      (node (ref "MODE") (pin "P$4") (pinfunction "P$2_P$4") (pintype "bidirectional"))
      (node (ref "U$3") (pin "37") (pinfunction "PF6(ADC6/TDO)_37") (pintype "bidirectional"))
    )
    (net (code "55") (name "UI_MODE_1.A") (class "Default")
      (node (ref "R7") (pin "P$2.1") (pinfunction "1_P$2.1") (pintype "passive"))
      (node (ref "U$3") (pin "25") (pinfunction "PD4(ICP1/ADC8)_25") (pintype "bidirectional"))
    )
    (net (code "56") (name "UI_MODE_1.B") (class "Default")
      (node (ref "R7") (pin "P$1.1") (pinfunction "1_P$1.1") (pintype "passive"))
      (node (ref "U$3") (pin "22") (pinfunction "PD5(XCK/_CTS)_22") (pintype "bidirectional"))
    )
    (net (code "57") (name "UI_MODE_2.A") (class "Default")
      (node (ref "R7") (pin "P$4.1") (pinfunction "1_P$4.1") (pintype "passive"))
      (node (ref "U$3") (pin "26") (pinfunction "PD6(T1/_OC4D/ADC9)_26") (pintype "bidirectional"))
    )
    (net (code "58") (name "UI_MODE_2.B") (class "Default")
      (node (ref "R7") (pin "P$3.1") (pinfunction "1_P$3.1") (pintype "passive"))
      (node (ref "U$3") (pin "27") (pinfunction "PD7(T0/OC4D/ADC10)_27") (pintype "bidirectional"))
    )
    (net (code "59") (name "UI_SCALE.A") (class "Default")
      (node (ref "JP1") (pin "2") (pinfunction "2_2") (pintype "passive"))
      (node (ref "R5") (pin "1") (pinfunction "1_1") (pintype "passive"))
      (node (ref "U$3") (pin "41") (pinfunction "PF0(ADC0)_41") (pintype "bidirectional"))
    )
    (net (code "60") (name "UI_THRESH") (class "Default")
      (node (ref "SEL") (pin "P2-2") (pinfunction "M_P2-2") (pintype "bidirectional"))
      (node (ref "U$3") (pin "39") (pinfunction "PF4(ADC4/TCK)_39") (pintype "bidirectional"))
    )
    (net (code "61") (name "UI_TRIGGER.A") (class "Default")
      (node (ref "R15") (pin "P$1.1") (pinfunction "1_P$1.1") (pintype "passive"))
      (node (ref "U$3") (pin "18") (pinfunction "PD0(OC0B/SCL/INT0)_18") (pintype "bidirectional"))
    )
    (net (code "62") (name "UI_TRIGGER.B") (class "Default")
      (node (ref "R15") (pin "P$2.1") (pinfunction "1_P$2.1") (pintype "passive"))
      (node (ref "U$3") (pin "19") (pinfunction "PD1(SDA/INT1)_19") (pintype "bidirectional"))
    )
    (net (code "63") (name "USB_D+") (class "Default")
      (node (ref "R1") (pin "P$1.2") (pinfunction "2_P$1.2") (pintype "passive"))
      (node (ref "U$3") (pin "4") (pinfunction "D+_4") (pintype "bidirectional"))
    )
    (net (code "64") (name "USB_D-") (class "Default")
      (node (ref "R1") (pin "P$2.2") (pinfunction "2_P$2.2") (pintype "passive"))
      (node (ref "U$3") (pin "3") (pinfunction "D-_3") (pintype "bidirectional"))
    )
    (net (code "65") (name "VBUS") (class "Default")
      (node (ref "D3") (pin "2") (pinfunction "A_2") (pintype "passive"))
      (node (ref "F1") (pin "2") (pinfunction "P$2_2") (pintype "bidirectional"))
      (node (ref "U$3") (pin "2") (pinfunction "UVCC_2") (pintype "bidirectional"))
      (node (ref "U$3") (pin "7") (pinfunction "VBUS_7") (pintype "bidirectional"))
    )
    (net (code "66") (name "XTAL1") (class "Default")
      (node (ref "IO7") (pin "TP") (pinfunction "TP_TP") (pintype "input"))
      (node (ref "U$3") (pin "17") (pinfunction "XTAL1_17") (pintype "bidirectional"))
    )
    (net (code "67") (name "XTAL2") (class "Default")
      (node (ref "IO8") (pin "TP") (pinfunction "TP_TP") (pintype "input"))
      (node (ref "U$3") (pin "16") (pinfunction "XTAL2_16") (pintype "bidirectional"))
    )
  )
)
